# FilterSchematic_REV2.net
KiCad netlist of a schematic drawn in EAGLE
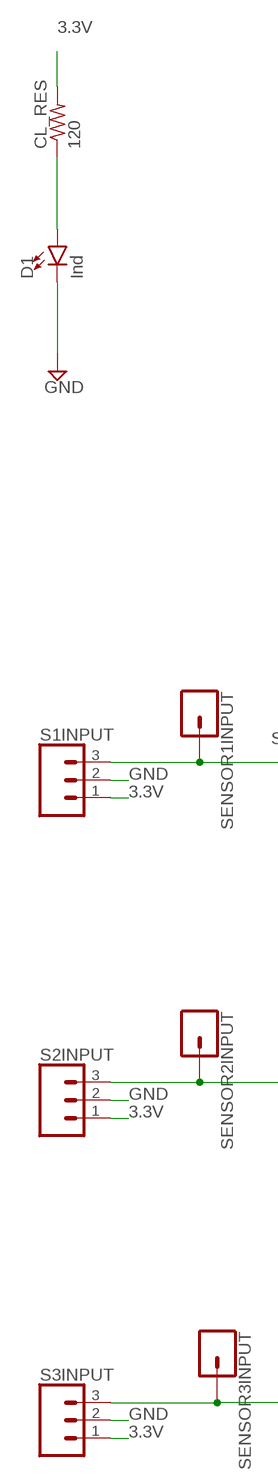
[diagram p0: schematic, sheet 1, part 1 of 2]
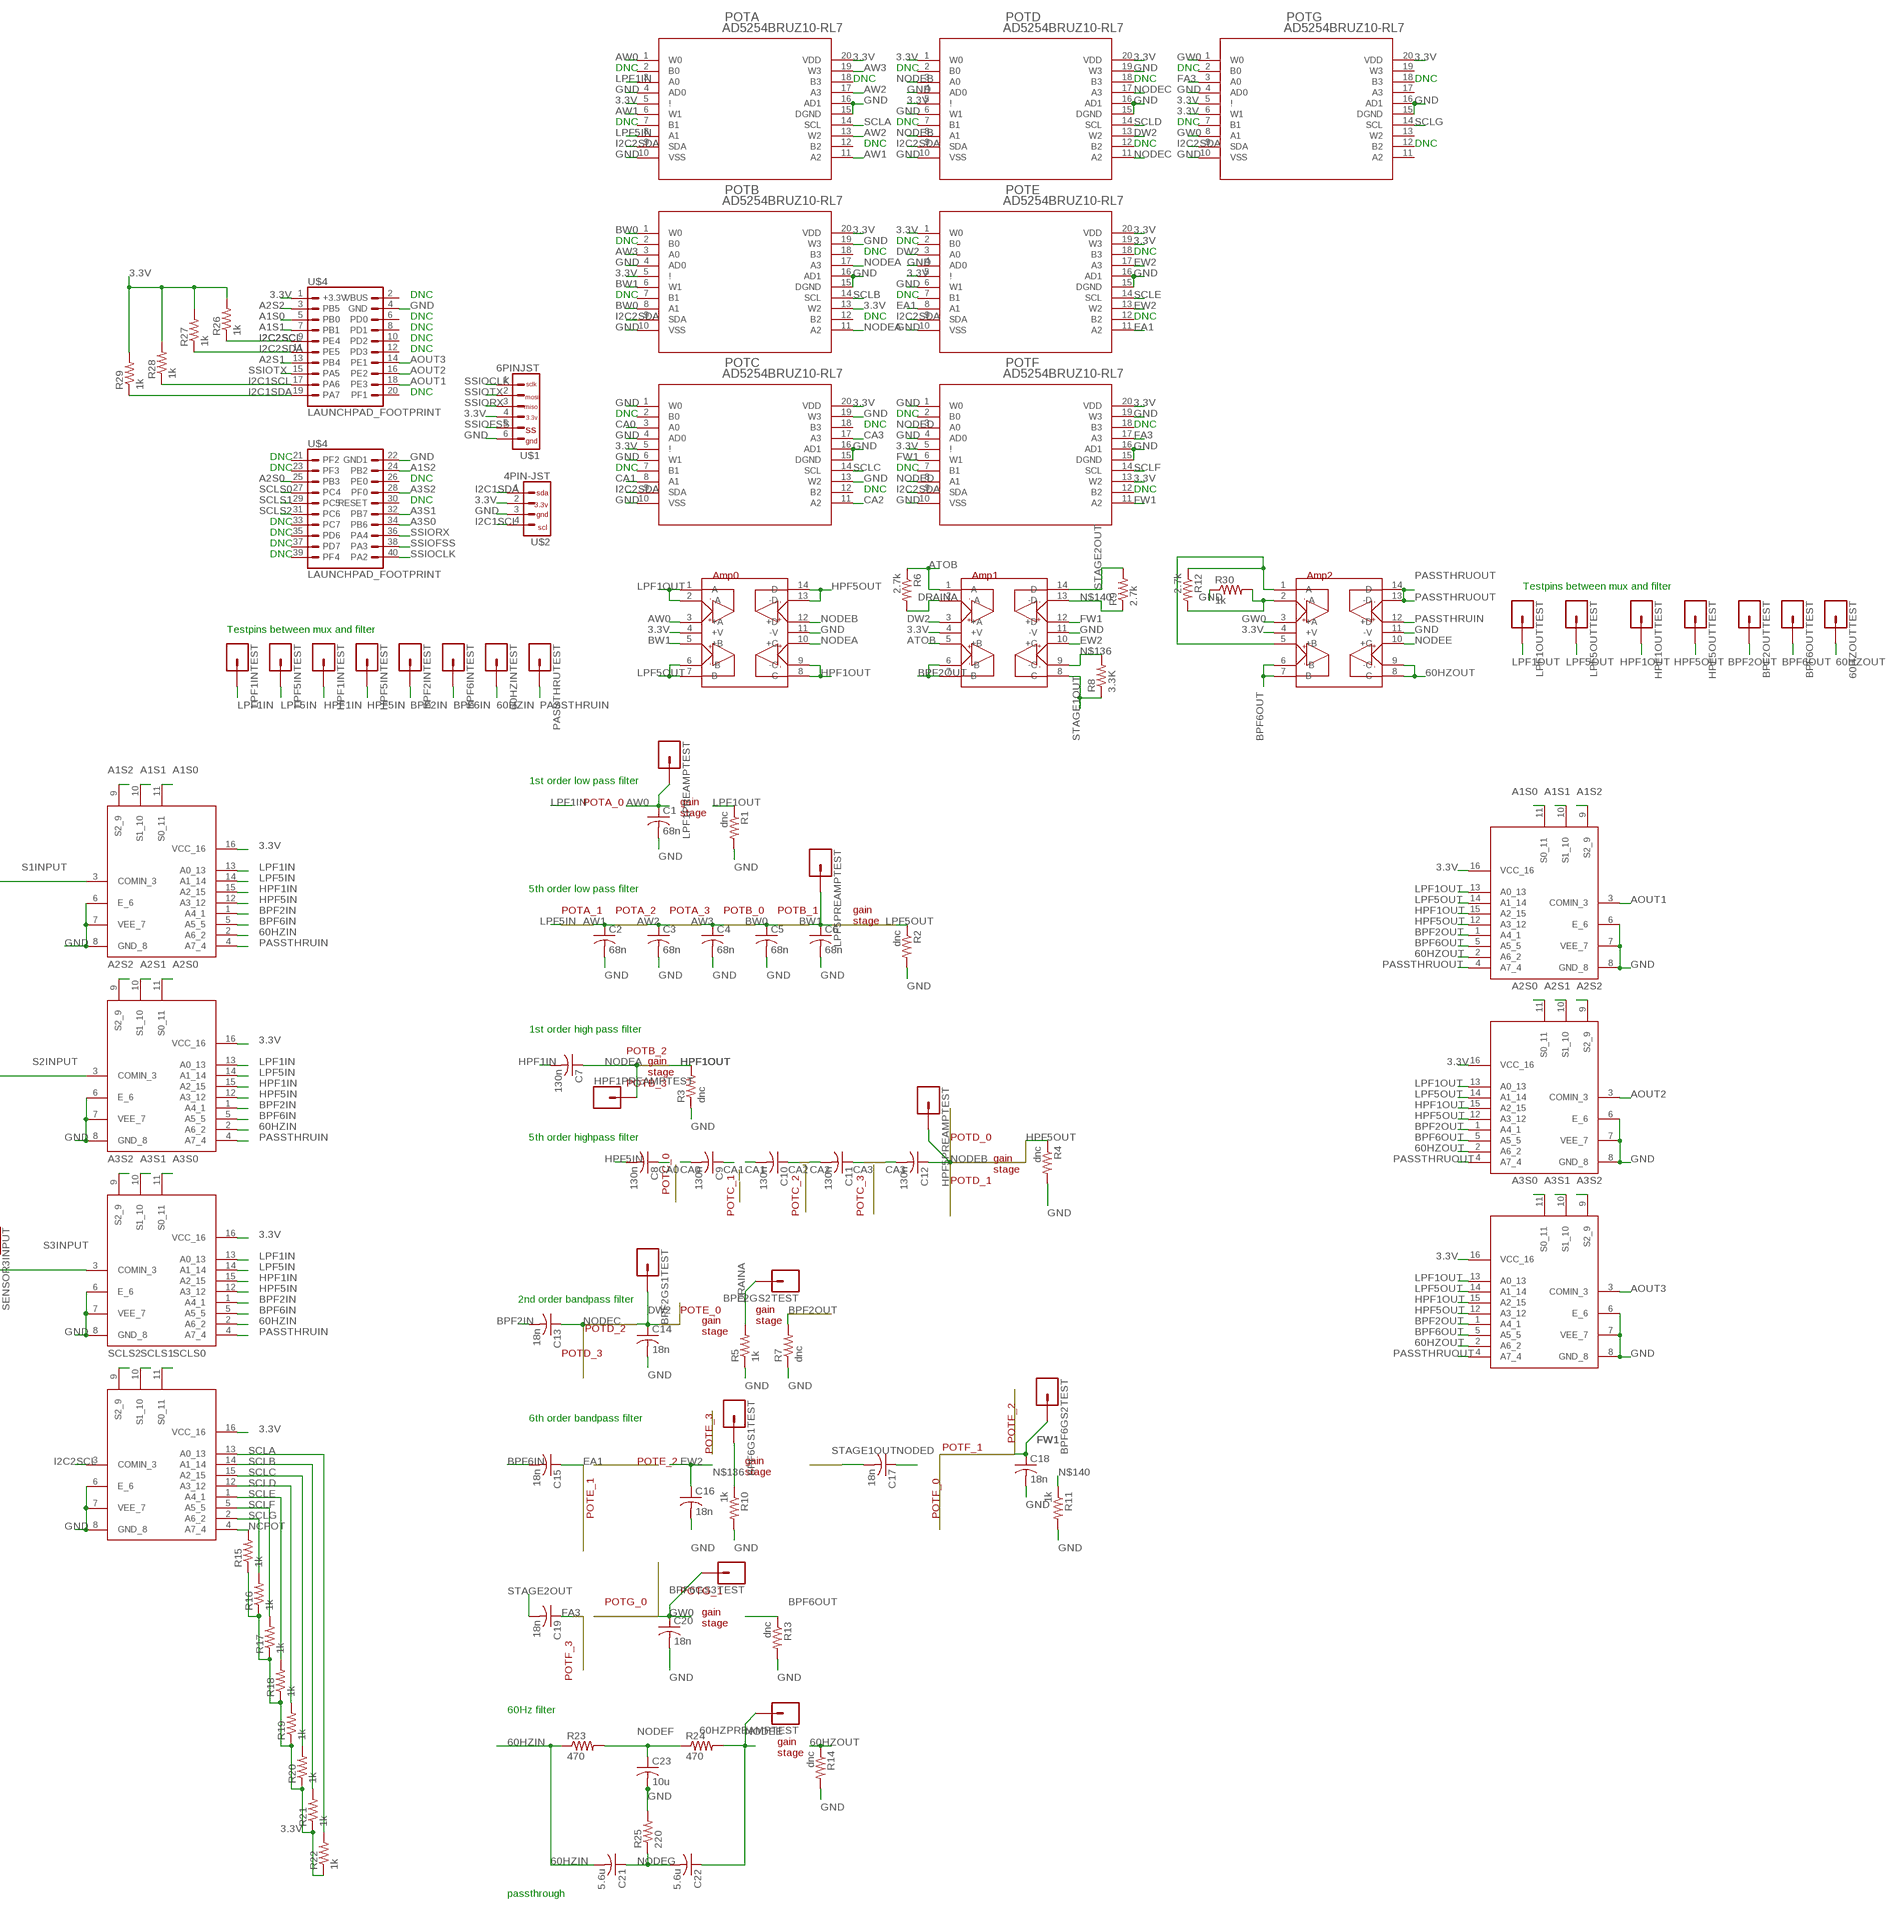
[diagram p1: schematic, sheet 1, part 2 of 2]

(export (version "E")
  (design (tool "Eeschema 10.0.6"))
  (components
    (comp (ref "60HZINTEST")
      (value "CONN_01")
      (footprint "eagle-import:1X01")
      (libsource (lib "eagle-import") (part "CONN_01"))
    )
    (comp (ref "60HZOUTTEST")
      (value "CONN_01")
      (footprint "eagle-import:1X01")
      (libsource (lib "eagle-import") (part "CONN_01"))
    )
    (comp (ref "60HZPREAMPTEST")
      (value "CONN_01")
      (footprint "eagle-import:1X01")
      (libsource (lib "eagle-import") (part "CONN_01"))
    )
    (comp (ref "A3IDEMUX")
      (value "CD74HC4051-Q1")
      (footprint "eagle-import:TSSOP16")
      (libsource (lib "eagle-import") (part "CD74HC4051-Q1"))
    )
    (comp (ref "AI1DEMUX")
      (value "CD74HC4051-Q1")
      (footprint "eagle-import:TSSOP16")
      (libsource (lib "eagle-import") (part "CD74HC4051-Q1"))
    )
    (comp (ref "AI2DEMUX")
      (value "CD74HC4051-Q1")
      (footprint "eagle-import:TSSOP16")
      (libsource (lib "eagle-import") (part "CD74HC4051-Q1"))
    )
    (comp (ref "AMP0")
      (value "OPA4830")
      (footprint "eagle-import:TSSOP14")
      (libsource (lib "eagle-import") (part "OPA4830"))
    )
    (comp (ref "AMP1")
      (value "OPA4830")
      (footprint "eagle-import:TSSOP14")
      (libsource (lib "eagle-import") (part "OPA4830"))
    )
    (comp (ref "AMP2")
      (value "OPA4830")
      (footprint "eagle-import:TSSOP14")
      (libsource (lib "eagle-import") (part "OPA4830"))
    )
    (comp (ref "AO1MUX")
      (value "CD74HC4051-Q1")
      (footprint "eagle-import:TSSOP16")
      (libsource (lib "eagle-import") (part "CD74HC4051-Q1"))
    )
    (comp (ref "AO2MUX")
      (value "CD74HC4051-Q1")
      (footprint "eagle-import:TSSOP16")
      (libsource (lib "eagle-import") (part "CD74HC4051-Q1"))
    )
    (comp (ref "AO3MUX")
      (value "CD74HC4051-Q1")
      (footprint "eagle-import:TSSOP16")
      (libsource (lib "eagle-import") (part "CD74HC4051-Q1"))
    )
    (comp (ref "BPF2GS1TEST")
      (value "CONN_01")
      (footprint "eagle-import:1X01")
      (libsource (lib "eagle-import") (part "CONN_01"))
    )
    (comp (ref "BPF2GS2TEST")
      (value "CONN_01")
      (footprint "eagle-import:1X01")
      (libsource (lib "eagle-import") (part "CONN_01"))
    )
    (comp (ref "BPF2INTEST")
      (value "CONN_01")
      (footprint "eagle-import:1X01")
      (libsource (lib "eagle-import") (part "CONN_01"))
    )
    (comp (ref "BPF2OUTTEST")
      (value "CONN_01")
      (footprint "eagle-import:1X01")
      (libsource (lib "eagle-import") (part "CONN_01"))
    )
    (comp (ref "BPF6GS1TEST")
      (value "CONN_01")
      (footprint "eagle-import:1X01")
      (libsource (lib "eagle-import") (part "CONN_01"))
    )
    (comp (ref "BPF6GS2TEST")
      (value "CONN_01")
      (footprint "eagle-import:1X01")
      (libsource (lib "eagle-import") (part "CONN_01"))
    )
    (comp (ref "BPF6GS3TEST")
      (value "CONN_01")
      (footprint "eagle-import:1X01")
      (libsource (lib "eagle-import") (part "CONN_01"))
    )
    (comp (ref "BPF6INTEST")
      (value "CONN_01")
      (footprint "eagle-import:1X01")
      (libsource (lib "eagle-import") (part "CONN_01"))
    )
    (comp (ref "BPF6OUTTEST")
      (value "CONN_01")
      (footprint "eagle-import:1X01")
      (libsource (lib "eagle-import") (part "CONN_01"))
    )
    (comp (ref "C1")
      (value "68n")
      (footprint "eagle-import:C0805")
      (libsource (lib "eagle-import") (part "C-USC0805"))
    )
    (comp (ref "C2")
      (value "68n")
      (footprint "eagle-import:C0805")
      (libsource (lib "eagle-import") (part "C-USC0805"))
    )
    (comp (ref "C3")
      (value "68n")
      (footprint "eagle-import:C0805")
      (libsource (lib "eagle-import") (part "C-USC0805"))
    )
    (comp (ref "C4")
      (value "68n")
      (footprint "eagle-import:C0805")
      (libsource (lib "eagle-import") (part "C-USC0805"))
    )
    (comp (ref "C5")
      (value "68n")
      (footprint "eagle-import:C0805")
      (libsource (lib "eagle-import") (part "C-USC0805"))
    )
    (comp (ref "C6")
      (value "68n")
      (footprint "eagle-import:C0805")
      (libsource (lib "eagle-import") (part "C-USC0805"))
    )
    (comp (ref "C7")
      (value "130n")
      (footprint "eagle-import:C0805")
      (libsource (lib "eagle-import") (part "C-USC0805"))
    )
    (comp (ref "C8")
      (value "130n")
      (footprint "eagle-import:C0805")
      (libsource (lib "eagle-import") (part "C-USC0805"))
    )
    (comp (ref "C9")
      (value "130n")
      (footprint "eagle-import:C0805")
      (libsource (lib "eagle-import") (part "C-USC0805"))
    )
    (comp (ref "C10")
      (value "130n")
      (footprint "eagle-import:C0805")
      (libsource (lib "eagle-import") (part "C-USC0805"))
    )
    (comp (ref "C11")
      (value "130n")
      (footprint "eagle-import:C0805")
      (libsource (lib "eagle-import") (part "C-USC0805"))
    )
    (comp (ref "C12")
      (value "130n")
      (footprint "eagle-import:C0805")
      (libsource (lib "eagle-import") (part "C-USC0805"))
    )
    (comp (ref "C13")
      (value "18n")
      (footprint "eagle-import:C0805")
      (libsource (lib "eagle-import") (part "C-USC0805"))
    )
    (comp (ref "C14")
      (value "18n")
      (footprint "eagle-import:C0805")
      (libsource (lib "eagle-import") (part "C-USC0805"))
    )
    (comp (ref "C15")
      (value "18n")
      (footprint "eagle-import:C0805")
      (libsource (lib "eagle-import") (part "C-USC0805"))
    )
    (comp (ref "C16")
      (value "18n")
      (footprint "eagle-import:C0805")
      (libsource (lib "eagle-import") (part "C-USC0805"))
    )
    (comp (ref "C17")
      (value "18n")
      (footprint "eagle-import:C0805")
      (libsource (lib "eagle-import") (part "C-USC0805"))
    )
    (comp (ref "C18")
      (value "18n")
      (footprint "eagle-import:C0805")
      (libsource (lib "eagle-import") (part "C-USC0805"))
    )
    (comp (ref "C19")
      (value "18n")
      (footprint "eagle-import:C0805")
      (libsource (lib "eagle-import") (part "C-USC0805"))
    )
    (comp (ref "C20")
      (value "18n")
      (footprint "eagle-import:C0805")
      (libsource (lib "eagle-import") (part "C-USC0805"))
    )
    (comp (ref "C21")
      (value "5.6u")
      (footprint "eagle-import:C0805")
      (libsource (lib "eagle-import") (part "C-USC0805"))
    )
    (comp (ref "C22")
      (value "5.6u")
      (footprint "eagle-import:C0805")
      (libsource (lib "eagle-import") (part "C-USC0805"))
    )
    (comp (ref "C23")
      (value "10u")
      (footprint "eagle-import:C0805")
      (libsource (lib "eagle-import") (part "C-USC0805"))
    )
    (comp (ref "CL_RES")
      (value "120")
      (footprint "eagle-import:R0805")
      (libsource (lib "eagle-import") (part "rcl_334_R-US_R0805"))
    )
    (comp (ref "D1")
      (value "Ind")
      (footprint "eagle-import:LED-0603")
      (libsource (lib "eagle-import") (part "LED-GREEN0603"))
    )
    (comp (ref "HPF1INTEST")
      (value "CONN_01")
      (footprint "eagle-import:1X01")
      (libsource (lib "eagle-import") (part "CONN_01"))
    )
    (comp (ref "HPF1OUTTEST")
      (value "CONN_01")
      (footprint "eagle-import:1X01")
      (libsource (lib "eagle-import") (part "CONN_01"))
    )
    (comp (ref "HPF1PREAMPTEST")
      (value "CONN_01")
      (footprint "eagle-import:1X01")
      (libsource (lib "eagle-import") (part "CONN_01"))
    )
    (comp (ref "HPF5INTEST")
      (value "CONN_01")
      (footprint "eagle-import:1X01")
      (libsource (lib "eagle-import") (part "CONN_01"))
    )
    (comp (ref "HPF5OUTTEST")
      (value "CONN_01")
      (footprint "eagle-import:1X01")
      (libsource (lib "eagle-import") (part "CONN_01"))
    )
    (comp (ref "HPF5PREAMPTEST")
      (value "CONN_01")
      (footprint "eagle-import:1X01")
      (libsource (lib "eagle-import") (part "CONN_01"))
    )
    (comp (ref "LPF1INTEST")
      (value "CONN_01")
      (footprint "eagle-import:1X01")
      (libsource (lib "eagle-import") (part "CONN_01"))
    )
    (comp (ref "LPF1OUTTEST")
      (value "CONN_01")
      (footprint "eagle-import:1X01")
      (libsource (lib "eagle-import") (part "CONN_01"))
    )
    (comp (ref "LPF1PREAMPTEST")
      (value "CONN_01")
      (footprint "eagle-import:1X01")
      (libsource (lib "eagle-import") (part "CONN_01"))
    )
    (comp (ref "LPF5INTEST")
      (value "CONN_01")
      (footprint "eagle-import:1X01")
      (libsource (lib "eagle-import") (part "CONN_01"))
    )
    (comp (ref "LPF5OUTTEST")
      (value "CONN_01")
      (footprint "eagle-import:1X01")
      (libsource (lib "eagle-import") (part "CONN_01"))
    )
    (comp (ref "LPF5PREAMPTEST")
      (value "CONN_01")
      (footprint "eagle-import:1X01")
      (libsource (lib "eagle-import") (part "CONN_01"))
    )
    (comp (ref "PASSTHRUTEST")
      (value "CONN_01")
      (footprint "eagle-import:1X01")
      (libsource (lib "eagle-import") (part "CONN_01"))
    )
    (comp (ref "POTA")
      (value "AD5254BRUZ10-RL7")
      (footprint "eagle-import:RU_20")
      (fields (field (name "MANUFACTURER_PART_NUMBER") "AD5254BRUZ10RL7"))
      (libsource (lib "eagle-import") (part "AD5254BRUZ10-RL7"))
    )
    (comp (ref "POTB")
      (value "AD5254BRUZ10-RL7")
      (footprint "eagle-import:RU_20")
      (fields (field (name "MANUFACTURER_PART_NUMBER") "AD5254BRUZ10RL7"))
      (libsource (lib "eagle-import") (part "AD5254BRUZ10-RL7"))
    )
    (comp (ref "POTC")
      (value "AD5254BRUZ10-RL7")
      (footprint "eagle-import:RU_20")
      (fields (field (name "MANUFACTURER_PART_NUMBER") "AD5254BRUZ10RL7"))
      (libsource (lib "eagle-import") (part "AD5254BRUZ10-RL7"))
    )
    (comp (ref "POTD")
      (value "AD5254BRUZ10-RL7")
      (footprint "eagle-import:RU_20")
      (fields (field (name "MANUFACTURER_PART_NUMBER") "AD5254BRUZ10RL7"))
      (libsource (lib "eagle-import") (part "AD5254BRUZ10-RL7"))
    )
    (comp (ref "POTE")
      (value "AD5254BRUZ10-RL7")
      (footprint "eagle-import:RU_20")
      (fields (field (name "MANUFACTURER_PART_NUMBER") "AD5254BRUZ10RL7"))
      (libsource (lib "eagle-import") (part "AD5254BRUZ10-RL7"))
    )
    (comp (ref "POTF")
      (value "AD5254BRUZ10-RL7")
      (footprint "eagle-import:RU_20")
      (fields (field (name "MANUFACTURER_PART_NUMBER") "AD5254BRUZ10RL7"))
      (libsource (lib "eagle-import") (part "AD5254BRUZ10-RL7"))
    )
    (comp (ref "POTG")
      (value "AD5254BRUZ10-RL7")
      (footprint "eagle-import:RU_20")
      (fields (field (name "MANUFACTURER_PART_NUMBER") "AD5254BRUZ10RL7"))
      (libsource (lib "eagle-import") (part "AD5254BRUZ10-RL7"))
    )
    (comp (ref "R1")
      (value "dnc")
      (footprint "eagle-import:R0805")
      (libsource (lib "eagle-import") (part "rcl_334_R-US_R0805"))
    )
    (comp (ref "R2")
      (value "dnc")
      (footprint "eagle-import:R0805")
      (libsource (lib "eagle-import") (part "rcl_334_R-US_R0805"))
    )
    (comp (ref "R3")
      (value "dnc")
      (footprint "eagle-import:R0805")
      (libsource (lib "eagle-import") (part "rcl_334_R-US_R0805"))
    )
    (comp (ref "R4")
      (value "dnc")
      (footprint "eagle-import:R0805")
      (libsource (lib "eagle-import") (part "rcl_334_R-US_R0805"))
    )
    (comp (ref "R5")
      (value "1k")
      (footprint "eagle-import:R0805")
      (libsource (lib "eagle-import") (part "rcl_334_R-US_R0805"))
    )
    (comp (ref "R6")
      (value "2.7k")
      (footprint "eagle-import:R0805")
      (libsource (lib "eagle-import") (part "rcl_334_R-US_R0805"))
    )
    (comp (ref "R7")
      (value "dnc")
      (footprint "eagle-import:R0805")
      (libsource (lib "eagle-import") (part "rcl_334_R-US_R0805"))
    )
    (comp (ref "R8")
      (value "3.3K")
      (footprint "eagle-import:R0805")
      (libsource (lib "eagle-import") (part "rcl_334_R-US_R0805"))
    )
    (comp (ref "R9")
      (value "2.7k")
      (footprint "eagle-import:R0805")
      (libsource (lib "eagle-import") (part "rcl_334_R-US_R0805"))
    )
    (comp (ref "R10")
      (value "1k")
      (footprint "eagle-import:R0805")
      (libsource (lib "eagle-import") (part "rcl_334_R-US_R0805"))
    )
    (comp (ref "R11")
      (value "1k")
      (footprint "eagle-import:R0805")
      (libsource (lib "eagle-import") (part "rcl_334_R-US_R0805"))
    )
    (comp (ref "R12")
      (value "2.7k")
      (footprint "eagle-import:R0805")
      (libsource (lib "eagle-import") (part "rcl_334_R-US_R0805"))
    )
    (comp (ref "R13")
      (value "dnc")
      (footprint "eagle-import:R0805")
      (libsource (lib "eagle-import") (part "rcl_334_R-US_R0805"))
    )
    (comp (ref "R14")
      (value "dnc")
      (footprint "eagle-import:R0805")
      (libsource (lib "eagle-import") (part "rcl_334_R-US_R0805"))
    )
    (comp (ref "R15")
      (value "1k")
      (footprint "eagle-import:R0805")
      (libsource (lib "eagle-import") (part "rcl_334_R-US_R0805"))
    )
    (comp (ref "R16")
      (value "1k")
      (footprint "eagle-import:R0805")
      (libsource (lib "eagle-import") (part "rcl_334_R-US_R0805"))
    )
    (comp (ref "R17")
      (value "1k")
      (footprint "eagle-import:R0805")
      (libsource (lib "eagle-import") (part "rcl_334_R-US_R0805"))
    )
    (comp (ref "R18")
      (value "1k")
      (footprint "eagle-import:R0805")
      (libsource (lib "eagle-import") (part "rcl_334_R-US_R0805"))
    )
    (comp (ref "R19")
      (value "1k")
      (footprint "eagle-import:R0805")
      (libsource (lib "eagle-import") (part "rcl_334_R-US_R0805"))
    )
    (comp (ref "R20")
      (value "1k")
      (footprint "eagle-import:R0805")
      (libsource (lib "eagle-import") (part "rcl_334_R-US_R0805"))
    )
    (comp (ref "R21")
      (value "1k")
      (footprint "eagle-import:R0805")
      (libsource (lib "eagle-import") (part "rcl_334_R-US_R0805"))
    )
    (comp (ref "R22")
      (value "1k")
      (footprint "eagle-import:R0805")
      (libsource (lib "eagle-import") (part "rcl_334_R-US_R0805"))
    )
    (comp (ref "R23")
      (value "470")
      (footprint "eagle-import:R0805")
      (libsource (lib "eagle-import") (part "R-US_R0805"))
    )
    (comp (ref "R24")
      (value "470")
      (footprint "eagle-import:R0805")
      (libsource (lib "eagle-import") (part "R-US_R0805"))
    )
    (comp (ref "R25")
      (value "220")
      (footprint "eagle-import:R0805")
      (libsource (lib "eagle-import") (part "R-US_R0805"))
    )
    (comp (ref "R26")
      (value "1k")
      (footprint "eagle-import:R0805")
      (libsource (lib "eagle-import") (part "rcl_334_R-US_R0805"))
    )
    (comp (ref "R27")
      (value "1k")
      (footprint "eagle-import:R0805")
      (libsource (lib "eagle-import") (part "rcl_334_R-US_R0805"))
    )
    (comp (ref "R28")
      (value "1k")
      (footprint "eagle-import:R0805")
      (libsource (lib "eagle-import") (part "rcl_334_R-US_R0805"))
    )
    (comp (ref "R29")
      (value "1k")
      (footprint "eagle-import:R0805")
      (libsource (lib "eagle-import") (part "rcl_334_R-US_R0805"))
    )
    (comp (ref "R30")
      (value "1k")
      (footprint "eagle-import:R0805")
      (libsource (lib "eagle-import") (part "rcl_334_R-US_R0805"))
    )
    (comp (ref "S1INPUT")
      (value "CONN_03JST-PTH-VERT")
      (footprint "eagle-import:JST-3-PTH-VERT")
      (libsource (lib "eagle-import") (part "CONN_03JST-PTH-VERT"))
    )
    (comp (ref "S2INPUT")
      (value "CONN_03JST-PTH-VERT")
      (footprint "eagle-import:JST-3-PTH-VERT")
      (libsource (lib "eagle-import") (part "CONN_03JST-PTH-VERT"))
    )
    (comp (ref "S3INPUT")
      (value "CONN_03JST-PTH-VERT")
      (footprint "eagle-import:JST-3-PTH-VERT")
      (libsource (lib "eagle-import") (part "CONN_03JST-PTH-VERT"))
    )
    (comp (ref "SCLMUX")
      (value "CD74HC4051-Q1")
      (footprint "eagle-import:TSSOP16")
      (libsource (lib "eagle-import") (part "CD74HC4051-Q1"))
    )
    (comp (ref "SENSOR1INPUT")
      (value "CONN_01")
      (footprint "eagle-import:1X01")
      (libsource (lib "eagle-import") (part "CONN_01"))
    )
    (comp (ref "SENSOR2INPUT")
      (value "CONN_01")
      (footprint "eagle-import:1X01")
      (libsource (lib "eagle-import") (part "CONN_01"))
    )
    (comp (ref "SENSOR3INPUT")
      (value "CONN_01")
      (footprint "eagle-import:1X01")
      (libsource (lib "eagle-import") (part "CONN_01"))
    )
    (comp (ref "U$1")
      (value "6PINJST")
      (footprint "eagle-import:JST-6-PTH-VERT")
      (libsource (lib "eagle-import") (part "6PINJST"))
    )
    (comp (ref "U$2")
      (value "4PIN-JST")
      (footprint "eagle-import:JST-4-PTH-VERT")
      (libsource (lib "eagle-import") (part "4PIN-JST"))
    )
    (comp (ref "U$4")
      (value "LAUNCHPAD_FOOTPRINT")
      (footprint "eagle-import:SSW-110-02-S-D")
      (libsource (lib "eagle-import") (part "LAUNCHPAD_FOOTPRINT"))
    )
  )
  (nets
    (net (code "1") (name "/3.3V") (class "Default")
      (node (ref "A3IDEMUX") (pin "16") (pinfunction "VCC_16_16") (pintype "bidirectional"))
      (node (ref "AI1DEMUX") (pin "16") (pinfunction "VCC_16_16") (pintype "bidirectional"))
      (node (ref "AI2DEMUX") (pin "16") (pinfunction "VCC_16_16") (pintype "bidirectional"))
      (node (ref "AMP0") (pin "4") (pinfunction "+V_4") (pintype "bidirectional"))
      (node (ref "AMP1") (pin "4") (pinfunction "+V_4") (pintype "bidirectional"))
      (node (ref "AMP2") (pin "4") (pinfunction "+V_4") (pintype "bidirectional"))
      (node (ref "AO1MUX") (pin "16") (pinfunction "VCC_16_16") (pintype "bidirectional"))
      (node (ref "AO2MUX") (pin "16") (pinfunction "VCC_16_16") (pintype "bidirectional"))
      (node (ref "AO3MUX") (pin "16") (pinfunction "VCC_16_16") (pintype "bidirectional"))
      (node (ref "CL_RES") (pin "2") (pinfunction "2_2") (pintype "passive"))
      (node (ref "POTA") (pin "20") (pinfunction "VDD_20") (pintype "power_in"))
      (node (ref "POTA") (pin "5") (pinfunction "~_5") (pintype "passive"))
      (node (ref "POTB") (pin "13") (pinfunction "W2_13") (pintype "passive"))
      (node (ref "POTB") (pin "20") (pinfunction "VDD_20") (pintype "power_in"))
      (node (ref "POTB") (pin "5") (pinfunction "~_5") (pintype "passive"))
      (node (ref "POTC") (pin "20") (pinfunction "VDD_20") (pintype "power_in"))
      (node (ref "POTC") (pin "5") (pinfunction "~_5") (pintype "passive"))
      (node (ref "POTD") (pin "1") (pinfunction "W0_1") (pintype "passive"))
      (node (ref "POTD") (pin "20") (pinfunction "VDD_20") (pintype "power_in"))
      (node (ref "POTD") (pin "5") (pinfunction "~_5") (pintype "passive"))
      (node (ref "POTE") (pin "1") (pinfunction "W0_1") (pintype "passive"))
      (node (ref "POTE") (pin "19") (pinfunction "W3_19") (pintype "passive"))
      (node (ref "POTE") (pin "20") (pinfunction "VDD_20") (pintype "power_in"))
      (node (ref "POTE") (pin "5") (pinfunction "~_5") (pintype "passive"))
      (node (ref "POTF") (pin "13") (pinfunction "W2_13") (pintype "passive"))
      (node (ref "POTF") (pin "20") (pinfunction "VDD_20") (pintype "power_in"))
      (node (ref "POTF") (pin "5") (pinfunction "~_5") (pintype "passive"))
      (node (ref "POTG") (pin "20") (pinfunction "VDD_20") (pintype "power_in"))
      (node (ref "POTG") (pin "5") (pinfunction "~_5") (pintype "passive"))
      (node (ref "POTG") (pin "6") (pinfunction "W1_6") (pintype "passive"))
      (node (ref "R15") (pin "1") (pinfunction "1_1") (pintype "passive"))
      (node (ref "R16") (pin "1") (pinfunction "1_1") (pintype "passive"))
      (node (ref "R17") (pin "1") (pinfunction "1_1") (pintype "passive"))
      (node (ref "R18") (pin "1") (pinfunction "1_1") (pintype "passive"))
      (node (ref "R19") (pin "1") (pinfunction "1_1") (pintype "passive"))
      (node (ref "R20") (pin "1") (pinfunction "1_1") (pintype "passive"))
      (node (ref "R21") (pin "1") (pinfunction "1_1") (pintype "passive"))
      (node (ref "R22") (pin "1") (pinfunction "1_1") (pintype "passive"))
      (node (ref "R26") (pin "2") (pinfunction "2_2") (pintype "passive"))
      (node (ref "R27") (pin "2") (pinfunction "2_2") (pintype "passive"))
      (node (ref "R28") (pin "2") (pinfunction "2_2") (pintype "passive"))
      (node (ref "R29") (pin "2") (pinfunction "2_2") (pintype "passive"))
      (node (ref "S1INPUT") (pin "1") (pinfunction "1_1") (pintype "passive"))
      (node (ref "S2INPUT") (pin "1") (pinfunction "1_1") (pintype "passive"))
      (node (ref "S3INPUT") (pin "1") (pinfunction "1_1") (pintype "passive"))
      (node (ref "SCLMUX") (pin "16") (pinfunction "VCC_16_16") (pintype "bidirectional"))
      (node (ref "U$1") (pin "4") (pinfunction "4_4") (pintype "passive"))
      (node (ref "U$2") (pin "2") (pinfunction "2_2") (pintype "passive"))
      (node (ref "U$4") (pin "1") (pinfunction "+3.3V_1") (pintype "passive"))
    )
    (net (code "2") (name "/60HZIN") (class "Default")
      (node (ref "60HZINTEST") (pin "1") (pinfunction "1_1") (pintype "passive"))
      (node (ref "A3IDEMUX") (pin "2") (pinfunction "A6_2_2") (pintype "bidirectional"))
      (node (ref "AI1DEMUX") (pin "2") (pinfunction "A6_2_2") (pintype "bidirectional"))
      (node (ref "AI2DEMUX") (pin "2") (pinfunction "A6_2_2") (pintype "bidirectional"))
      (node (ref "C21") (pin "2") (pinfunction "2_2") (pintype "passive"))
      (node (ref "R23") (pin "1") (pinfunction "1_1") (pintype "passive"))
    )
    (net (code "3") (name "/60HZOUT") (class "Default")
      (node (ref "60HZOUTTEST") (pin "1") (pinfunction "1_1") (pintype "passive"))
      (node (ref "AMP2") (pin "8") (pinfunction "C_8") (pintype "bidirectional"))
      (node (ref "AMP2") (pin "9") (pinfunction "-C_9") (pintype "bidirectional"))
      (node (ref "AO1MUX") (pin "2") (pinfunction "A6_2_2") (pintype "bidirectional"))
      (node (ref "AO2MUX") (pin "2") (pinfunction "A6_2_2") (pintype "bidirectional"))
      (node (ref "AO3MUX") (pin "2") (pinfunction "A6_2_2") (pintype "bidirectional"))
      (node (ref "R14") (pin "1") (pinfunction "1_1") (pintype "passive"))
    )
    (net (code "4") (name "/A1S0") (class "Default")
      (node (ref "AI1DEMUX") (pin "11") (pinfunction "S0_11_11") (pintype "bidirectional"))
      (node (ref "AO1MUX") (pin "11") (pinfunction "S0_11_11") (pintype "bidirectional"))
      (node (ref "U$4") (pin "5") (pinfunction "PB0_5") (pintype "passive"))
    )
    (net (code "5") (name "/A1S1") (class "Default")
      (node (ref "AI1DEMUX") (pin "10") (pinfunction "S1_10_10") (pintype "bidirectional"))
      (node (ref "AO1MUX") (pin "10") (pinfunction "S1_10_10") (pintype "bidirectional"))
      (node (ref "U$4") (pin "7") (pinfunction "PB1_7") (pintype "passive"))
    )
    (net (code "6") (name "/A1S2") (class "Default")
      (node (ref "AI1DEMUX") (pin "9") (pinfunction "S2_9_9") (pintype "bidirectional"))
      (node (ref "AO1MUX") (pin "9") (pinfunction "S2_9_9") (pintype "bidirectional"))
      (node (ref "U$4") (pin "24") (pinfunction "PB2_24") (pintype "passive"))
    )
    (net (code "7") (name "/A2S0") (class "Default")
      (node (ref "AI2DEMUX") (pin "11") (pinfunction "S0_11_11") (pintype "bidirectional"))
      (node (ref "AO2MUX") (pin "11") (pinfunction "S0_11_11") (pintype "bidirectional"))
      (node (ref "U$4") (pin "25") (pinfunction "PB3_25") (pintype "passive"))
    )
    (net (code "8") (name "/A2S1") (class "Default")
      (node (ref "AI2DEMUX") (pin "10") (pinfunction "S1_10_10") (pintype "bidirectional"))
      (node (ref "AO2MUX") (pin "10") (pinfunction "S1_10_10") (pintype "bidirectional"))
      (node (ref "U$4") (pin "13") (pinfunction "PB4_13") (pintype "passive"))
    )
    (net (code "9") (name "/A2S2") (class "Default")
      (node (ref "AI2DEMUX") (pin "9") (pinfunction "S2_9_9") (pintype "bidirectional"))
      (node (ref "AO2MUX") (pin "9") (pinfunction "S2_9_9") (pintype "bidirectional"))
      (node (ref "U$4") (pin "3") (pinfunction "PB5_3") (pintype "passive"))
    )
    (net (code "10") (name "/A3S0") (class "Default")
      (node (ref "A3IDEMUX") (pin "11") (pinfunction "S0_11_11") (pintype "bidirectional"))
      (node (ref "AO3MUX") (pin "11") (pinfunction "S0_11_11") (pintype "bidirectional"))
      (node (ref "U$4") (pin "34") (pinfunction "PB6_34") (pintype "passive"))
    )
    (net (code "11") (name "/A3S1") (class "Default")
      (node (ref "A3IDEMUX") (pin "10") (pinfunction "S1_10_10") (pintype "bidirectional"))
      (node (ref "AO3MUX") (pin "10") (pinfunction "S1_10_10") (pintype "bidirectional"))
      (node (ref "U$4") (pin "32") (pinfunction "PB7_32") (pintype "passive"))
    )
    (net (code "12") (name "/A3S2") (class "Default")
      (node (ref "A3IDEMUX") (pin "9") (pinfunction "S2_9_9") (pintype "bidirectional"))
      (node (ref "AO3MUX") (pin "9") (pinfunction "S2_9_9") (pintype "bidirectional"))
      (node (ref "U$4") (pin "28") (pinfunction "PF0_28") (pintype "passive"))
    )
    (net (code "13") (name "/AOUT1") (class "Default")
      (node (ref "AO1MUX") (pin "3") (pinfunction "COMIN_3_3") (pintype "bidirectional"))
      (node (ref "U$4") (pin "18") (pinfunction "PE3_18") (pintype "passive"))
    )
    (net (code "14") (name "/AOUT2") (class "Default")
      (node (ref "AO2MUX") (pin "3") (pinfunction "COMIN_3_3") (pintype "bidirectional"))
      (node (ref "U$4") (pin "16") (pinfunction "PE2_16") (pintype "passive"))
    )
    (net (code "15") (name "/AOUT3") (class "Default")
      (node (ref "AO3MUX") (pin "3") (pinfunction "COMIN_3_3") (pintype "bidirectional"))
      (node (ref "U$4") (pin "14") (pinfunction "PE1_14") (pintype "passive"))
    )
    (net (code "16") (name "/ATOB") (class "Default")
      (node (ref "AMP1") (pin "1") (pinfunction "A_1") (pintype "bidirectional"))
      (node (ref "AMP1") (pin "5") (pinfunction "+B_5") (pintype "bidirectional"))
      (node (ref "R6") (pin "1") (pinfunction "1_1") (pintype "passive"))
    )
    (net (code "17") (name "/AW0") (class "Default")
      (node (ref "AMP0") (pin "3") (pinfunction "+A_3") (pintype "bidirectional"))
      (node (ref "C1") (pin "1") (pinfunction "1_1") (pintype "passive"))
      (node (ref "LPF1PREAMPTEST") (pin "1") (pinfunction "1_1") (pintype "passive"))
      (node (ref "POTA") (pin "1") (pinfunction "W0_1") (pintype "passive"))
    )
    (net (code "18") (name "/AW1") (class "Default")
      (node (ref "C2") (pin "1") (pinfunction "1_1") (pintype "passive"))
      (node (ref "POTA") (pin "11") (pinfunction "A2_11") (pintype "passive"))
      (node (ref "POTA") (pin "6") (pinfunction "W1_6") (pintype "passive"))
    )
    (net (code "19") (name "/AW2") (class "Default")
      (node (ref "C3") (pin "1") (pinfunction "1_1") (pintype "passive"))
      (node (ref "POTA") (pin "13") (pinfunction "W2_13") (pintype "passive"))
      (node (ref "POTA") (pin "17") (pinfunction "A3_17") (pintype "passive"))
    )
    (net (code "20") (name "/AW3") (class "Default")
      (node (ref "C4") (pin "1") (pinfunction "1_1") (pintype "passive"))
      (node (ref "POTA") (pin "19") (pinfunction "W3_19") (pintype "passive"))
      (node (ref "POTB") (pin "3") (pinfunction "A0_3") (pintype "passive"))
    )
    (net (code "21") (name "/BPF2IN") (class "Default")
      (node (ref "A3IDEMUX") (pin "1") (pinfunction "A4_1_1") (pintype "bidirectional"))
      (node (ref "AI1DEMUX") (pin "1") (pinfunction "A4_1_1") (pintype "bidirectional"))
      (node (ref "AI2DEMUX") (pin "1") (pinfunction "A4_1_1") (pintype "bidirectional"))
      (node (ref "BPF2INTEST") (pin "1") (pinfunction "1_1") (pintype "passive"))
      (node (ref "C13") (pin "2") (pinfunction "2_2") (pintype "passive"))
    )
    (net (code "22") (name "/BPF2OUT") (class "Default")
      (node (ref "AMP1") (pin "6") (pinfunction "-B_6") (pintype "bidirectional"))
      (node (ref "AMP1") (pin "7") (pinfunction "B_7") (pintype "bidirectional"))
      (node (ref "AO1MUX") (pin "1") (pinfunction "A4_1_1") (pintype "bidirectional"))
      (node (ref "AO2MUX") (pin "1") (pinfunction "A4_1_1") (pintype "bidirectional"))
      (node (ref "AO3MUX") (pin "1") (pinfunction "A4_1_1") (pintype "bidirectional"))
      (node (ref "BPF2OUTTEST") (pin "1") (pinfunction "1_1") (pintype "passive"))
      (node (ref "R7") (pin "2") (pinfunction "2_2") (pintype "passive"))
    )
    (net (code "23") (name "/BPF6IN") (class "Default")
      (node (ref "A3IDEMUX") (pin "5") (pinfunction "A5_5_5") (pintype "bidirectional"))
      (node (ref "AI1DEMUX") (pin "5") (pinfunction "A5_5_5") (pintype "bidirectional"))
      (node (ref "AI2DEMUX") (pin "5") (pinfunction "A5_5_5") (pintype "bidirectional"))
      (node (ref "BPF6INTEST") (pin "1") (pinfunction "1_1") (pintype "passive"))
      (node (ref "C15") (pin "2") (pinfunction "2_2") (pintype "passive"))
    )
    (net (code "24") (name "/BPF6OUT") (class "Default")
      (node (ref "AMP2") (pin "6") (pinfunction "-B_6") (pintype "bidirectional"))
      (node (ref "AMP2") (pin "7") (pinfunction "B_7") (pintype "bidirectional"))
      (node (ref "AO1MUX") (pin "5") (pinfunction "A5_5_5") (pintype "bidirectional"))
      (node (ref "AO2MUX") (pin "5") (pinfunction "A5_5_5") (pintype "bidirectional"))
      (node (ref "AO3MUX") (pin "5") (pinfunction "A5_5_5") (pintype "bidirectional"))
      (node (ref "BPF6OUTTEST") (pin "1") (pinfunction "1_1") (pintype "passive"))
      (node (ref "R13") (pin "1") (pinfunction "1_1") (pintype "passive"))
    )
    (net (code "25") (name "/BW0") (class "Default")
      (node (ref "C5") (pin "1") (pinfunction "1_1") (pintype "passive"))
      (node (ref "POTB") (pin "1") (pinfunction "W0_1") (pintype "passive"))
      (node (ref "POTB") (pin "8") (pinfunction "A1_8") (pintype "passive"))
    )
    (net (code "26") (name "/BW1") (class "Default")
      (node (ref "AMP0") (pin "5") (pinfunction "+B_5") (pintype "bidirectional"))
      (node (ref "C6") (pin "1") (pinfunction "1_1") (pintype "passive"))
      (node (ref "LPF5PREAMPTEST") (pin "1") (pinfunction "1_1") (pintype "passive"))
      (node (ref "POTB") (pin "6") (pinfunction "W1_6") (pintype "passive"))
    )
    (net (code "27") (name "/CA0") (class "Default")
      (node (ref "C8") (pin "1") (pinfunction "1_1") (pintype "passive"))
      (node (ref "C9") (pin "2") (pinfunction "2_2") (pintype "passive"))
      (node (ref "POTC") (pin "3") (pinfunction "A0_3") (pintype "passive"))
    )
    (net (code "28") (name "/CA1") (class "Default")
      (node (ref "C10") (pin "2") (pinfunction "2_2") (pintype "passive"))
      (node (ref "C9") (pin "1") (pinfunction "1_1") (pintype "passive"))
      (node (ref "POTC") (pin "8") (pinfunction "A1_8") (pintype "passive"))
    )
    (net (code "29") (name "/CA2") (class "Default")
      (node (ref "C10") (pin "1") (pinfunction "1_1") (pintype "passive"))
      (node (ref "C11") (pin "2") (pinfunction "2_2") (pintype "passive"))
      (node (ref "POTC") (pin "11") (pinfunction "A2_11") (pintype "passive"))
    )
    (net (code "30") (name "/CA3") (class "Default")
      (node (ref "C11") (pin "1") (pinfunction "1_1") (pintype "passive"))
      (node (ref "C12") (pin "2") (pinfunction "2_2") (pintype "passive"))
      (node (ref "POTC") (pin "17") (pinfunction "A3_17") (pintype "passive"))
    )
    (net (code "31") (name "/DRAINA") (class "Default")
      (node (ref "AMP1") (pin "2") (pinfunction "-A_2") (pintype "bidirectional"))
      (node (ref "BPF2GS2TEST") (pin "1") (pinfunction "1_1") (pintype "passive"))
      (node (ref "R5") (pin "2") (pinfunction "2_2") (pintype "passive"))
      (node (ref "R6") (pin "2") (pinfunction "2_2") (pintype "passive"))
    )
    (net (code "32") (name "/DW2") (class "Default")
      (node (ref "AMP1") (pin "3") (pinfunction "+A_3") (pintype "bidirectional"))
      (node (ref "BPF2GS1TEST") (pin "1") (pinfunction "1_1") (pintype "passive"))
      (node (ref "C14") (pin "1") (pinfunction "1_1") (pintype "passive"))
      (node (ref "POTD") (pin "13") (pinfunction "W2_13") (pintype "passive"))
      (node (ref "POTE") (pin "3") (pinfunction "A0_3") (pintype "passive"))
    )
    (net (code "33") (name "/EA1") (class "Default")
      (node (ref "C15") (pin "1") (pinfunction "1_1") (pintype "passive"))
      (node (ref "POTE") (pin "11") (pinfunction "A2_11") (pintype "passive"))
      (node (ref "POTE") (pin "8") (pinfunction "A1_8") (pintype "passive"))
    )
    (net (code "34") (name "/EW2") (class "Default")
      (node (ref "AMP1") (pin "10") (pinfunction "+C_10") (pintype "bidirectional"))
      (node (ref "C16") (pin "1") (pinfunction "1_1") (pintype "passive"))
      (node (ref "POTE") (pin "13") (pinfunction "W2_13") (pintype "passive"))
      (node (ref "POTE") (pin "17") (pinfunction "A3_17") (pintype "passive"))
    )
    (net (code "35") (name "/FA3") (class "Default")
      (node (ref "C19") (pin "1") (pinfunction "1_1") (pintype "passive"))
      (node (ref "POTF") (pin "17") (pinfunction "A3_17") (pintype "passive"))
      (node (ref "POTG") (pin "3") (pinfunction "A0_3") (pintype "passive"))
    )
    (net (code "36") (name "/FW1") (class "Default")
      (node (ref "AMP1") (pin "12") (pinfunction "+D_12") (pintype "bidirectional"))
      (node (ref "BPF6GS2TEST") (pin "1") (pinfunction "1_1") (pintype "passive"))
      (node (ref "C18") (pin "1") (pinfunction "1_1") (pintype "passive"))
      (node (ref "POTF") (pin "11") (pinfunction "A2_11") (pintype "passive"))
      (node (ref "POTF") (pin "6") (pinfunction "W1_6") (pintype "passive"))
    )
    (net (code "37") (name "/GW0") (class "Default")
      (node (ref "AMP2") (pin "3") (pinfunction "+A_3") (pintype "bidirectional"))
      (node (ref "BPF6GS3TEST") (pin "1") (pinfunction "1_1") (pintype "passive"))
      (node (ref "C20") (pin "1") (pinfunction "1_1") (pintype "passive"))
      (node (ref "POTG") (pin "1") (pinfunction "W0_1") (pintype "passive"))
      (node (ref "POTG") (pin "8") (pinfunction "A1_8") (pintype "passive"))
    )
    (net (code "38") (name "/HPF1IN") (class "Default")
      (node (ref "A3IDEMUX") (pin "15") (pinfunction "A2_15_15") (pintype "bidirectional"))
      (node (ref "AI1DEMUX") (pin "15") (pinfunction "A2_15_15") (pintype "bidirectional"))
      (node (ref "AI2DEMUX") (pin "15") (pinfunction "A2_15_15") (pintype "bidirectional"))
      (node (ref "C7") (pin "2") (pinfunction "2_2") (pintype "passive"))
      (node (ref "HPF1INTEST") (pin "1") (pinfunction "1_1") (pintype "passive"))
    )
    (net (code "39") (name "/HPF1OUT") (class "Default")
      (node (ref "AMP0") (pin "8") (pinfunction "C_8") (pintype "bidirectional"))
      (node (ref "AMP0") (pin "9") (pinfunction "-C_9") (pintype "bidirectional"))
      (node (ref "AO1MUX") (pin "15") (pinfunction "A2_15_15") (pintype "bidirectional"))
      (node (ref "AO2MUX") (pin "15") (pinfunction "A2_15_15") (pintype "bidirectional"))
      (node (ref "AO3MUX") (pin "15") (pinfunction "A2_15_15") (pintype "bidirectional"))
      (node (ref "HPF1OUTTEST") (pin "1") (pinfunction "1_1") (pintype "passive"))
      (node (ref "R3") (pin "2") (pinfunction "2_2") (pintype "passive"))
    )
    (net (code "40") (name "/HPF5IN") (class "Default")
      (node (ref "A3IDEMUX") (pin "12") (pinfunction "A3_12_12") (pintype "bidirectional"))
      (node (ref "AI1DEMUX") (pin "12") (pinfunction "A3_12_12") (pintype "bidirectional"))
      (node (ref "AI2DEMUX") (pin "12") (pinfunction "A3_12_12") (pintype "bidirectional"))
      (node (ref "C8") (pin "2") (pinfunction "2_2") (pintype "passive"))
      (node (ref "HPF5INTEST") (pin "1") (pinfunction "1_1") (pintype "passive"))
    )
    (net (code "41") (name "/HPF5OUT") (class "Default")
      (node (ref "AMP0") (pin "13") (pinfunction "-D_13") (pintype "bidirectional"))
      (node (ref "AMP0") (pin "14") (pinfunction "D_14") (pintype "bidirectional"))
      (node (ref "AO1MUX") (pin "12") (pinfunction "A3_12_12") (pintype "bidirectional"))
      (node (ref "AO2MUX") (pin "12") (pinfunction "A3_12_12") (pintype "bidirectional"))
      (node (ref "AO3MUX") (pin "12") (pinfunction "A3_12_12") (pintype "bidirectional"))
      (node (ref "HPF5OUTTEST") (pin "1") (pinfunction "1_1") (pintype "passive"))
      (node (ref "R4") (pin "1") (pinfunction "1_1") (pintype "passive"))
    )
    (net (code "42") (name "/I2C1SCL") (class "Default")
      (node (ref "R28") (pin "1") (pinfunction "1_1") (pintype "passive"))
      (node (ref "U$2") (pin "4") (pinfunction "4_4") (pintype "passive"))
      (node (ref "U$4") (pin "17") (pinfunction "PA6_17") (pintype "passive"))
    )
    (net (code "43") (name "/I2C1SDA") (class "Default")
      (node (ref "R29") (pin "1") (pinfunction "1_1") (pintype "passive"))
      (node (ref "U$2") (pin "1") (pinfunction "1_1") (pintype "passive"))
      (node (ref "U$4") (pin "19") (pinfunction "PA7_19") (pintype "passive"))
    )
    (net (code "44") (name "/I2C2SCL") (class "Default")
      (node (ref "R26") (pin "1") (pinfunction "1_1") (pintype "passive"))
      (node (ref "SCLMUX") (pin "3") (pinfunction "COMIN_3_3") (pintype "bidirectional"))
      (node (ref "U$4") (pin "9") (pinfunction "PE4_9") (pintype "passive"))
    )
    (net (code "45") (name "/I2C2SDA") (class "Default")
      (node (ref "POTA") (pin "9") (pinfunction "SDA_9") (pintype "passive"))
      (node (ref "POTB") (pin "9") (pinfunction "SDA_9") (pintype "passive"))
      (node (ref "POTC") (pin "9") (pinfunction "SDA_9") (pintype "passive"))
      (node (ref "POTD") (pin "9") (pinfunction "SDA_9") (pintype "passive"))
      (node (ref "POTE") (pin "9") (pinfunction "SDA_9") (pintype "passive"))
      (node (ref "POTF") (pin "9") (pinfunction "SDA_9") (pintype "passive"))
      (node (ref "POTG") (pin "9") (pinfunction "SDA_9") (pintype "passive"))
      (node (ref "R27") (pin "1") (pinfunction "1_1") (pintype "passive"))
      (node (ref "U$4") (pin "11") (pinfunction "PE5_11") (pintype "passive"))
    )
    (net (code "46") (name "/LPF1IN") (class "Default")
      (node (ref "A3IDEMUX") (pin "13") (pinfunction "A0_13_13") (pintype "bidirectional"))
      (node (ref "AI1DEMUX") (pin "13") (pinfunction "A0_13_13") (pintype "bidirectional"))
      (node (ref "AI2DEMUX") (pin "13") (pinfunction "A0_13_13") (pintype "bidirectional"))
      (node (ref "LPF1INTEST") (pin "1") (pinfunction "1_1") (pintype "passive"))
      (node (ref "POTA") (pin "3") (pinfunction "A0_3") (pintype "passive"))
    )
    (net (code "47") (name "/LPF1OUT") (class "Default")
      (node (ref "AMP0") (pin "1") (pinfunction "A_1") (pintype "bidirectional"))
      (node (ref "AMP0") (pin "2") (pinfunction "-A_2") (pintype "bidirectional"))
      (node (ref "AO1MUX") (pin "13") (pinfunction "A0_13_13") (pintype "bidirectional"))
      (node (ref "AO2MUX") (pin "13") (pinfunction "A0_13_13") (pintype "bidirectional"))
      (node (ref "AO3MUX") (pin "13") (pinfunction "A0_13_13") (pintype "bidirectional"))
      (node (ref "LPF1OUTTEST") (pin "1") (pinfunction "1_1") (pintype "passive"))
      (node (ref "R1") (pin "1") (pinfunction "1_1") (pintype "passive"))
    )
    (net (code "48") (name "/LPF5IN") (class "Default")
      (node (ref "A3IDEMUX") (pin "14") (pinfunction "A1_14_14") (pintype "bidirectional"))
      (node (ref "AI1DEMUX") (pin "14") (pinfunction "A1_14_14") (pintype "bidirectional"))
      (node (ref "AI2DEMUX") (pin "14") (pinfunction "A1_14_14") (pintype "bidirectional"))
      (node (ref "LPF5INTEST") (pin "1") (pinfunction "1_1") (pintype "passive"))
      (node (ref "POTA") (pin "8") (pinfunction "A1_8") (pintype "passive"))
    )
    (net (code "49") (name "/LPF5OUT") (class "Default")
      (node (ref "AMP0") (pin "6") (pinfunction "-B_6") (pintype "bidirectional"))
      (node (ref "AMP0") (pin "7") (pinfunction "B_7") (pintype "bidirectional"))
      (node (ref "AO1MUX") (pin "14") (pinfunction "A1_14_14") (pintype "bidirectional"))
      (node (ref "AO2MUX") (pin "14") (pinfunction "A1_14_14") (pintype "bidirectional"))
      (node (ref "AO3MUX") (pin "14") (pinfunction "A1_14_14") (pintype "bidirectional"))
      (node (ref "LPF5OUTTEST") (pin "1") (pinfunction "1_1") (pintype "passive"))
      (node (ref "R2") (pin "1") (pinfunction "1_1") (pintype "passive"))
    )
    (net (code "50") (name "/N$136") (class "Default")
      (node (ref "AMP1") (pin "9") (pinfunction "-C_9") (pintype "bidirectional"))
      (node (ref "BPF6GS1TEST") (pin "1") (pinfunction "1_1") (pintype "passive"))
      (node (ref "R10") (pin "1") (pinfunction "1_1") (pintype "passive"))
      (node (ref "R8") (pin "2") (pinfunction "2_2") (pintype "passive"))
    )
    (net (code "51") (name "/N$140") (class "Default")
      (node (ref "AMP1") (pin "13") (pinfunction "-D_13") (pintype "bidirectional"))
      (node (ref "R11") (pin "1") (pinfunction "1_1") (pintype "passive"))
      (node (ref "R9") (pin "1") (pinfunction "1_1") (pintype "passive"))
    )
    (net (code "52") (name "/NCPOT") (class "Default")
      (node (ref "R15") (pin "2") (pinfunction "2_2") (pintype "passive"))
      (node (ref "SCLMUX") (pin "4") (pinfunction "A7_4_4") (pintype "bidirectional"))
    )
    (net (code "53") (name "/NODEA") (class "Default")
      (node (ref "AMP0") (pin "10") (pinfunction "+C_10") (pintype "bidirectional"))
      (node (ref "C7") (pin "1") (pinfunction "1_1") (pintype "passive"))
      (node (ref "HPF1PREAMPTEST") (pin "1") (pinfunction "1_1") (pintype "passive"))
      (node (ref "POTB") (pin "11") (pinfunction "A2_11") (pintype "passive"))
      (node (ref "POTB") (pin "17") (pinfunction "A3_17") (pintype "passive"))
    )
    (net (code "54") (name "/NODEB") (class "Default")
      (node (ref "AMP0") (pin "12") (pinfunction "+D_12") (pintype "bidirectional"))
      (node (ref "C12") (pin "1") (pinfunction "1_1") (pintype "passive"))
      (node (ref "HPF5PREAMPTEST") (pin "1") (pinfunction "1_1") (pintype "passive"))
      (node (ref "POTD") (pin "3") (pinfunction "A0_3") (pintype "passive"))
      (node (ref "POTD") (pin "8") (pinfunction "A1_8") (pintype "passive"))
    )
    (net (code "55") (name "/NODEC") (class "Default")
      (node (ref "C13") (pin "1") (pinfunction "1_1") (pintype "passive"))
      (node (ref "POTD") (pin "11") (pinfunction "A2_11") (pintype "passive"))
      (node (ref "POTD") (pin "17") (pinfunction "A3_17") (pintype "passive"))
    )
    (net (code "56") (name "/NODED") (class "Default")
      (node (ref "C17") (pin "1") (pinfunction "1_1") (pintype "passive"))
      (node (ref "POTF") (pin "3") (pinfunction "A0_3") (pintype "passive"))
      (node (ref "POTF") (pin "8") (pinfunction "A1_8") (pintype "passive"))
    )
    (net (code "57") (name "/NODEE") (class "Default")
      (node (ref "60HZPREAMPTEST") (pin "1") (pinfunction "1_1") (pintype "passive"))
      (node (ref "AMP2") (pin "10") (pinfunction "+C_10") (pintype "bidirectional"))
      (node (ref "C22") (pin "1") (pinfunction "1_1") (pintype "passive"))
      (node (ref "R24") (pin "2") (pinfunction "2_2") (pintype "passive"))
    )
    (net (code "58") (name "/NODEF") (class "Default")
      (node (ref "C23") (pin "1") (pinfunction "1_1") (pintype "passive"))
      (node (ref "R23") (pin "2") (pinfunction "2_2") (pintype "passive"))
      (node (ref "R24") (pin "1") (pinfunction "1_1") (pintype "passive"))
    )
    (net (code "59") (name "/NODEG") (class "Default")
      (node (ref "C21") (pin "1") (pinfunction "1_1") (pintype "passive"))
      (node (ref "C22") (pin "2") (pinfunction "2_2") (pintype "passive"))
      (node (ref "R25") (pin "1") (pinfunction "1_1") (pintype "passive"))
    )
    (net (code "60") (name "/PASSTHRUIN") (class "Default")
      (node (ref "A3IDEMUX") (pin "4") (pinfunction "A7_4_4") (pintype "bidirectional"))
      (node (ref "AI1DEMUX") (pin "4") (pinfunction "A7_4_4") (pintype "bidirectional"))
      (node (ref "AI2DEMUX") (pin "4") (pinfunction "A7_4_4") (pintype "bidirectional"))
      (node (ref "AMP2") (pin "12") (pinfunction "+D_12") (pintype "bidirectional"))
      (node (ref "PASSTHRUTEST") (pin "1") (pinfunction "1_1") (pintype "passive"))
    )
    (net (code "61") (name "/PASSTHRUOUT") (class "Default")
      (node (ref "AMP2") (pin "13") (pinfunction "-D_13") (pintype "bidirectional"))
      (node (ref "AMP2") (pin "14") (pinfunction "D_14") (pintype "bidirectional"))
      (node (ref "AO1MUX") (pin "4") (pinfunction "A7_4_4") (pintype "bidirectional"))
      (node (ref "AO2MUX") (pin "4") (pinfunction "A7_4_4") (pintype "bidirectional"))
      (node (ref "AO3MUX") (pin "4") (pinfunction "A7_4_4") (pintype "bidirectional"))
    )
    (net (code "62") (name "/S1INPUT") (class "Default")
      (node (ref "AI1DEMUX") (pin "3") (pinfunction "COMIN_3_3") (pintype "bidirectional"))
      (node (ref "S1INPUT") (pin "3") (pinfunction "3_3") (pintype "passive"))
      (node (ref "SENSOR1INPUT") (pin "1") (pinfunction "1_1") (pintype "passive"))
    )
    (net (code "63") (name "/S2INPUT") (class "Default")
      (node (ref "AI2DEMUX") (pin "3") (pinfunction "COMIN_3_3") (pintype "bidirectional"))
      (node (ref "S2INPUT") (pin "3") (pinfunction "3_3") (pintype "passive"))
      (node (ref "SENSOR2INPUT") (pin "1") (pinfunction "1_1") (pintype "passive"))
    )
    (net (code "64") (name "/S3INPUT") (class "Default")
      (node (ref "A3IDEMUX") (pin "3") (pinfunction "COMIN_3_3") (pintype "bidirectional"))
      (node (ref "S3INPUT") (pin "3") (pinfunction "3_3") (pintype "passive"))
      (node (ref "SENSOR3INPUT") (pin "1") (pinfunction "1_1") (pintype "passive"))
    )
    (net (code "65") (name "/SCLA") (class "Default")
      (node (ref "POTA") (pin "14") (pinfunction "SCL_14") (pintype "passive"))
      (node (ref "R22") (pin "2") (pinfunction "2_2") (pintype "passive"))
      (node (ref "SCLMUX") (pin "13") (pinfunction "A0_13_13") (pintype "bidirectional"))
    )
    (net (code "66") (name "/SCLB") (class "Default")
      (node (ref "POTB") (pin "14") (pinfunction "SCL_14") (pintype "passive"))
      (node (ref "R21") (pin "2") (pinfunction "2_2") (pintype "passive"))
      (node (ref "SCLMUX") (pin "14") (pinfunction "A1_14_14") (pintype "bidirectional"))
    )
    (net (code "67") (name "/SCLC") (class "Default")
      (node (ref "POTC") (pin "14") (pinfunction "SCL_14") (pintype "passive"))
      (node (ref "R20") (pin "2") (pinfunction "2_2") (pintype "passive"))
      (node (ref "SCLMUX") (pin "15") (pinfunction "A2_15_15") (pintype "bidirectional"))
    )
    (net (code "68") (name "/SCLD") (class "Default")
      (node (ref "POTD") (pin "14") (pinfunction "SCL_14") (pintype "passive"))
      (node (ref "R19") (pin "2") (pinfunction "2_2") (pintype "passive"))
      (node (ref "SCLMUX") (pin "12") (pinfunction "A3_12_12") (pintype "bidirectional"))
    )
    (net (code "69") (name "/SCLE") (class "Default")
      (node (ref "POTE") (pin "14") (pinfunction "SCL_14") (pintype "passive"))
      (node (ref "R18") (pin "2") (pinfunction "2_2") (pintype "passive"))
      (node (ref "SCLMUX") (pin "1") (pinfunction "A4_1_1") (pintype "bidirectional"))
    )
    (net (code "70") (name "/SCLF") (class "Default")
      (node (ref "POTF") (pin "14") (pinfunction "SCL_14") (pintype "passive"))
      (node (ref "R17") (pin "2") (pinfunction "2_2") (pintype "passive"))
      (node (ref "SCLMUX") (pin "5") (pinfunction "A5_5_5") (pintype "bidirectional"))
    )
    (net (code "71") (name "/SCLG") (class "Default")
      (node (ref "POTG") (pin "14") (pinfunction "SCL_14") (pintype "passive"))
      (node (ref "R16") (pin "2") (pinfunction "2_2") (pintype "passive"))
      (node (ref "SCLMUX") (pin "2") (pinfunction "A6_2_2") (pintype "bidirectional"))
    )
    (net (code "72") (name "/SCLS0") (class "Default")
      (node (ref "SCLMUX") (pin "11") (pinfunction "S0_11_11") (pintype "bidirectional"))
      (node (ref "U$4") (pin "27") (pinfunction "PC4_27") (pintype "passive"))
    )
    (net (code "73") (name "/SCLS1") (class "Default")
      (node (ref "SCLMUX") (pin "10") (pinfunction "S1_10_10") (pintype "bidirectional"))
      (node (ref "U$4") (pin "29") (pinfunction "PC5_29") (pintype "passive"))
    )
    (net (code "74") (name "/SCLS2") (class "Default")
      (node (ref "SCLMUX") (pin "9") (pinfunction "S2_9_9") (pintype "bidirectional"))
      (node (ref "U$4") (pin "31") (pinfunction "PC6_31") (pintype "passive"))
    )
    (net (code "75") (name "/SSIOCLK") (class "Default")
      (node (ref "U$1") (pin "1") (pinfunction "1_1") (pintype "passive"))
      (node (ref "U$4") (pin "40") (pinfunction "PA2_40") (pintype "passive"))
    )
    (net (code "76") (name "/SSIOFSS") (class "Default")
      (node (ref "U$1") (pin "5") (pinfunction "5_5") (pintype "passive"))
      (node (ref "U$4") (pin "38") (pinfunction "PA3_38") (pintype "passive"))
    )
    (net (code "77") (name "/SSIORX") (class "Default")
      (node (ref "U$1") (pin "3") (pinfunction "3_3") (pintype "passive"))
      (node (ref "U$4") (pin "36") (pinfunction "PA4_36") (pintype "passive"))
    )
    (net (code "78") (name "/SSIOTX") (class "Default")
      (node (ref "U$1") (pin "2") (pinfunction "2_2") (pintype "passive"))
      (node (ref "U$4") (pin "15") (pinfunction "PA5_15") (pintype "passive"))
    )
    (net (code "79") (name "/STAGE1OUT") (class "Default")
      (node (ref "AMP1") (pin "8") (pinfunction "C_8") (pintype "bidirectional"))
      (node (ref "C17") (pin "2") (pinfunction "2_2") (pintype "passive"))
      (node (ref "R8") (pin "1") (pinfunction "1_1") (pintype "passive"))
    )
    (net (code "80") (name "/STAGE2OUT") (class "Default")
      (node (ref "AMP1") (pin "14") (pinfunction "D_14") (pintype "bidirectional"))
      (node (ref "C19") (pin "2") (pinfunction "2_2") (pintype "passive"))
      (node (ref "R9") (pin "2") (pinfunction "2_2") (pintype "passive"))
    )
    (net (code "81") (name "GND") (class "Default")
      (node (ref "A3IDEMUX") (pin "6") (pinfunction "E_6_6") (pintype "bidirectional"))
      (node (ref "A3IDEMUX") (pin "7") (pinfunction "VEE_7_7") (pintype "bidirectional"))
      (node (ref "A3IDEMUX") (pin "8") (pinfunction "GND_8_8") (pintype "bidirectional"))
      (node (ref "AI1DEMUX") (pin "6") (pinfunction "E_6_6") (pintype "bidirectional"))
      (node (ref "AI1DEMUX") (pin "7") (pinfunction "VEE_7_7") (pintype "bidirectional"))
      (node (ref "AI1DEMUX") (pin "8") (pinfunction "GND_8_8") (pintype "bidirectional"))
      (node (ref "AI2DEMUX") (pin "6") (pinfunction "E_6_6") (pintype "bidirectional"))
      (node (ref "AI2DEMUX") (pin "7") (pinfunction "VEE_7_7") (pintype "bidirectional"))
      (node (ref "AI2DEMUX") (pin "8") (pinfunction "GND_8_8") (pintype "bidirectional"))
      (node (ref "AMP0") (pin "11") (pinfunction "-V_11") (pintype "bidirectional"))
      (node (ref "AMP1") (pin "11") (pinfunction "-V_11") (pintype "bidirectional"))
      (node (ref "AMP2") (pin "11") (pinfunction "-V_11") (pintype "bidirectional"))
      (node (ref "AO1MUX") (pin "6") (pinfunction "E_6_6") (pintype "bidirectional"))
      (node (ref "AO1MUX") (pin "7") (pinfunction "VEE_7_7") (pintype "bidirectional"))
      (node (ref "AO1MUX") (pin "8") (pinfunction "GND_8_8") (pintype "bidirectional"))
      (node (ref "AO2MUX") (pin "6") (pinfunction "E_6_6") (pintype "bidirectional"))
      (node (ref "AO2MUX") (pin "7") (pinfunction "VEE_7_7") (pintype "bidirectional"))
      (node (ref "AO2MUX") (pin "8") (pinfunction "GND_8_8") (pintype "bidirectional"))
      (node (ref "AO3MUX") (pin "6") (pinfunction "E_6_6") (pintype "bidirectional"))
      (node (ref "AO3MUX") (pin "7") (pinfunction "VEE_7_7") (pintype "bidirectional"))
      (node (ref "AO3MUX") (pin "8") (pinfunction "GND_8_8") (pintype "bidirectional"))
      (node (ref "C1") (pin "2") (pinfunction "2_2") (pintype "passive"))
      (node (ref "C14") (pin "2") (pinfunction "2_2") (pintype "passive"))
      (node (ref "C16") (pin "2") (pinfunction "2_2") (pintype "passive"))
      (node (ref "C18") (pin "2") (pinfunction "2_2") (pintype "passive"))
      (node (ref "C2") (pin "2") (pinfunction "2_2") (pintype "passive"))
      (node (ref "C20") (pin "2") (pinfunction "2_2") (pintype "passive"))
      (node (ref "C23") (pin "2") (pinfunction "2_2") (pintype "passive"))
      (node (ref "C3") (pin "2") (pinfunction "2_2") (pintype "passive"))
      (node (ref "C4") (pin "2") (pinfunction "2_2") (pintype "passive"))
      (node (ref "C5") (pin "2") (pinfunction "2_2") (pintype "passive"))
      (node (ref "C6") (pin "2") (pinfunction "2_2") (pintype "passive"))
      (node (ref "D1") (pin "C") (pinfunction "C_C") (pintype "passive"))
      (node (ref "POTA") (pin "10") (pinfunction "VSS_10") (pintype "power_in"))
      (node (ref "POTA") (pin "15") (pinfunction "DGND_15") (pintype "passive"))
      (node (ref "POTA") (pin "16") (pinfunction "AD1_16") (pintype "passive"))
      (node (ref "POTA") (pin "4") (pinfunction "AD0_4") (pintype "passive"))
      (node (ref "POTB") (pin "10") (pinfunction "VSS_10") (pintype "power_in"))
      (node (ref "POTB") (pin "15") (pinfunction "DGND_15") (pintype "passive"))
      (node (ref "POTB") (pin "16") (pinfunction "AD1_16") (pintype "passive"))
      (node (ref "POTB") (pin "19") (pinfunction "W3_19") (pintype "passive"))
      (node (ref "POTB") (pin "4") (pinfunction "AD0_4") (pintype "passive"))
      (node (ref "POTC") (pin "1") (pinfunction "W0_1") (pintype "passive"))
      (node (ref "POTC") (pin "10") (pinfunction "VSS_10") (pintype "power_in"))
      (node (ref "POTC") (pin "13") (pinfunction "W2_13") (pintype "passive"))
      (node (ref "POTC") (pin "15") (pinfunction "DGND_15") (pintype "passive"))
      (node (ref "POTC") (pin "16") (pinfunction "AD1_16") (pintype "passive"))
      (node (ref "POTC") (pin "19") (pinfunction "W3_19") (pintype "passive"))
      (node (ref "POTC") (pin "4") (pinfunction "AD0_4") (pintype "passive"))
      (node (ref "POTC") (pin "6") (pinfunction "W1_6") (pintype "passive"))
      (node (ref "POTD") (pin "10") (pinfunction "VSS_10") (pintype "power_in"))
      (node (ref "POTD") (pin "15") (pinfunction "DGND_15") (pintype "passive"))
      (node (ref "POTD") (pin "16") (pinfunction "AD1_16") (pintype "passive"))
      (node (ref "POTD") (pin "19") (pinfunction "W3_19") (pintype "passive"))
      (node (ref "POTD") (pin "4") (pinfunction "AD0_4") (pintype "passive"))
      (node (ref "POTD") (pin "6") (pinfunction "W1_6") (pintype "passive"))
      (node (ref "POTE") (pin "10") (pinfunction "VSS_10") (pintype "power_in"))
      (node (ref "POTE") (pin "15") (pinfunction "DGND_15") (pintype "passive"))
      (node (ref "POTE") (pin "16") (pinfunction "AD1_16") (pintype "passive"))
      (node (ref "POTE") (pin "4") (pinfunction "AD0_4") (pintype "passive"))
      (node (ref "POTE") (pin "6") (pinfunction "W1_6") (pintype "passive"))
      (node (ref "POTF") (pin "1") (pinfunction "W0_1") (pintype "passive"))
      (node (ref "POTF") (pin "10") (pinfunction "VSS_10") (pintype "power_in"))
      (node (ref "POTF") (pin "15") (pinfunction "DGND_15") (pintype "passive"))
      (node (ref "POTF") (pin "16") (pinfunction "AD1_16") (pintype "passive"))
      (node (ref "POTF") (pin "19") (pinfunction "W3_19") (pintype "passive"))
      (node (ref "POTF") (pin "4") (pinfunction "AD0_4") (pintype "passive"))
      (node (ref "POTG") (pin "10") (pinfunction "VSS_10") (pintype "power_in"))
      (node (ref "POTG") (pin "15") (pinfunction "DGND_15") (pintype "passive"))
      (node (ref "POTG") (pin "16") (pinfunction "AD1_16") (pintype "passive"))
      (node (ref "POTG") (pin "4") (pinfunction "AD0_4") (pintype "passive"))
      (node (ref "R1") (pin "2") (pinfunction "2_2") (pintype "passive"))
      (node (ref "R10") (pin "2") (pinfunction "2_2") (pintype "passive"))
      (node (ref "R11") (pin "2") (pinfunction "2_2") (pintype "passive"))
      (node (ref "R13") (pin "2") (pinfunction "2_2") (pintype "passive"))
      (node (ref "R14") (pin "2") (pinfunction "2_2") (pintype "passive"))
      (node (ref "R2") (pin "2") (pinfunction "2_2") (pintype "passive"))
      (node (ref "R25") (pin "2") (pinfunction "2_2") (pintype "passive"))
      (node (ref "R3") (pin "1") (pinfunction "1_1") (pintype "passive"))
      (node (ref "R30") (pin "1") (pinfunction "1_1") (pintype "passive"))
      (node (ref "R4") (pin "2") (pinfunction "2_2") (pintype "passive"))
      (node (ref "R5") (pin "1") (pinfunction "1_1") (pintype "passive"))
      (node (ref "R7") (pin "1") (pinfunction "1_1") (pintype "passive"))
      (node (ref "S1INPUT") (pin "2") (pinfunction "2_2") (pintype "passive"))
      (node (ref "S2INPUT") (pin "2") (pinfunction "2_2") (pintype "passive"))
      (node (ref "S3INPUT") (pin "2") (pinfunction "2_2") (pintype "passive"))
      (node (ref "SCLMUX") (pin "6") (pinfunction "E_6_6") (pintype "bidirectional"))
      (node (ref "SCLMUX") (pin "7") (pinfunction "VEE_7_7") (pintype "bidirectional"))
      (node (ref "SCLMUX") (pin "8") (pinfunction "GND_8_8") (pintype "bidirectional"))
      (node (ref "U$1") (pin "6") (pinfunction "6_6") (pintype "passive"))
      (node (ref "U$2") (pin "3") (pinfunction "3_3") (pintype "passive"))
      (node (ref "U$4") (pin "22") (pinfunction "GND1_22") (pintype "passive"))
      (node (ref "U$4") (pin "4") (pinfunction "GND_4") (pintype "passive"))
    )
    (net (code "82") (name "Net-(AMP2-+B)") (class "Default")
      (node (ref "AMP2") (pin "1") (pinfunction "A_1") (pintype "bidirectional"))
      (node (ref "AMP2") (pin "5") (pinfunction "+B_5") (pintype "bidirectional"))
      (node (ref "R12") (pin "1") (pinfunction "1_1") (pintype "passive"))
    )
    (net (code "83") (name "Net-(AMP2--A)") (class "Default")
      (node (ref "AMP2") (pin "2") (pinfunction "-A_2") (pintype "bidirectional"))
      (node (ref "R12") (pin "2") (pinfunction "2_2") (pintype "passive"))
      (node (ref "R30") (pin "2") (pinfunction "2_2") (pintype "passive"))
    )
    (net (code "84") (name "Net-(CL_RES-Pad1)") (class "Default")
      (node (ref "CL_RES") (pin "1") (pinfunction "1_1") (pintype "passive"))
      (node (ref "D1") (pin "A") (pinfunction "A_A") (pintype "passive"))
    )
    (net (code "85") (name "unconnected-(POTA-B0-Pad2)") (class "Default")
      (node (ref "POTA") (pin "2") (pinfunction "B0_2") (pintype "passive"))
    )
    (net (code "86") (name "unconnected-(POTA-B1-Pad7)") (class "Default")
      (node (ref "POTA") (pin "7") (pinfunction "B1_7") (pintype "passive"))
    )
    (net (code "87") (name "unconnected-(POTA-B2-Pad12)") (class "Default")
      (node (ref "POTA") (pin "12") (pinfunction "B2_12") (pintype "passive"))
    )
    (net (code "88") (name "unconnected-(POTA-B3-Pad18)") (class "Default")
      (node (ref "POTA") (pin "18") (pinfunction "B3_18") (pintype "passive"))
    )
    (net (code "89") (name "unconnected-(POTB-B0-Pad2)") (class "Default")
      (node (ref "POTB") (pin "2") (pinfunction "B0_2") (pintype "passive"))
    )
    (net (code "90") (name "unconnected-(POTB-B1-Pad7)") (class "Default")
      (node (ref "POTB") (pin "7") (pinfunction "B1_7") (pintype "passive"))
    )
    (net (code "91") (name "unconnected-(POTB-B2-Pad12)") (class "Default")
      (node (ref "POTB") (pin "12") (pinfunction "B2_12") (pintype "passive"))
    )
    (net (code "92") (name "unconnected-(POTB-B3-Pad18)") (class "Default")
      (node (ref "POTB") (pin "18") (pinfunction "B3_18") (pintype "passive"))
    )
    (net (code "93") (name "unconnected-(POTC-B0-Pad2)") (class "Default")
      (node (ref "POTC") (pin "2") (pinfunction "B0_2") (pintype "passive"))
    )
    (net (code "94") (name "unconnected-(POTC-B1-Pad7)") (class "Default")
      (node (ref "POTC") (pin "7") (pinfunction "B1_7") (pintype "passive"))
    )
    (net (code "95") (name "unconnected-(POTC-B2-Pad12)") (class "Default")
      (node (ref "POTC") (pin "12") (pinfunction "B2_12") (pintype "passive"))
    )
    (net (code "96") (name "unconnected-(POTC-B3-Pad18)") (class "Default")
      (node (ref "POTC") (pin "18") (pinfunction "B3_18") (pintype "passive"))
    )
    (net (code "97") (name "unconnected-(POTD-B0-Pad2)") (class "Default")
      (node (ref "POTD") (pin "2") (pinfunction "B0_2") (pintype "passive"))
    )
    (net (code "98") (name "unconnected-(POTD-B1-Pad7)") (class "Default")
      (node (ref "POTD") (pin "7") (pinfunction "B1_7") (pintype "passive"))
    )
    (net (code "99") (name "unconnected-(POTD-B2-Pad12)") (class "Default")
      (node (ref "POTD") (pin "12") (pinfunction "B2_12") (pintype "passive"))
    )
    (net (code "100") (name "unconnected-(POTD-B3-Pad18)") (class "Default")
      (node (ref "POTD") (pin "18") (pinfunction "B3_18") (pintype "passive"))
    )
    (net (code "101") (name "unconnected-(POTE-B0-Pad2)") (class "Default")
      (node (ref "POTE") (pin "2") (pinfunction "B0_2") (pintype "passive"))
    )
    (net (code "102") (name "unconnected-(POTE-B1-Pad7)") (class "Default")
      (node (ref "POTE") (pin "7") (pinfunction "B1_7") (pintype "passive"))
    )
    (net (code "103") (name "unconnected-(POTE-B2-Pad12)") (class "Default")
      (node (ref "POTE") (pin "12") (pinfunction "B2_12") (pintype "passive"))
    )
    (net (code "104") (name "unconnected-(POTE-B3-Pad18)") (class "Default")
      (node (ref "POTE") (pin "18") (pinfunction "B3_18") (pintype "passive"))
    )
    (net (code "105") (name "unconnected-(POTF-B0-Pad2)") (class "Default")
      (node (ref "POTF") (pin "2") (pinfunction "B0_2") (pintype "passive"))
    )
    (net (code "106") (name "unconnected-(POTF-B1-Pad7)") (class "Default")
      (node (ref "POTF") (pin "7") (pinfunction "B1_7") (pintype "passive"))
    )
    (net (code "107") (name "unconnected-(POTF-B2-Pad12)") (class "Default")
      (node (ref "POTF") (pin "12") (pinfunction "B2_12") (pintype "passive"))
    )
    (net (code "108") (name "unconnected-(POTF-B3-Pad18)") (class "Default")
      (node (ref "POTF") (pin "18") (pinfunction "B3_18") (pintype "passive"))
    )
    (net (code "109") (name "unconnected-(POTG-A2-Pad11)") (class "Default")
      (node (ref "POTG") (pin "11") (pinfunction "A2_11") (pintype "passive"))
    )
    (net (code "110") (name "unconnected-(POTG-A3-Pad17)") (class "Default")
      (node (ref "POTG") (pin "17") (pinfunction "A3_17") (pintype "passive"))
    )
    (net (code "111") (name "unconnected-(POTG-B0-Pad2)") (class "Default")
      (node (ref "POTG") (pin "2") (pinfunction "B0_2") (pintype "passive"))
    )
    (net (code "112") (name "unconnected-(POTG-B1-Pad7)") (class "Default")
      (node (ref "POTG") (pin "7") (pinfunction "B1_7") (pintype "passive"))
    )
    (net (code "113") (name "unconnected-(POTG-B2-Pad12)") (class "Default")
      (node (ref "POTG") (pin "12") (pinfunction "B2_12") (pintype "passive"))
    )
    (net (code "114") (name "unconnected-(POTG-B3-Pad18)") (class "Default")
      (node (ref "POTG") (pin "18") (pinfunction "B3_18") (pintype "passive"))
    )
    (net (code "115") (name "unconnected-(POTG-W2-Pad13)") (class "Default")
      (node (ref "POTG") (pin "13") (pinfunction "W2_13") (pintype "passive"))
    )
    (net (code "116") (name "unconnected-(POTG-W3-Pad19)") (class "Default")
      (node (ref "POTG") (pin "19") (pinfunction "W3_19") (pintype "passive"))
    )
    (net (code "117") (name "unconnected-(U$4-PC7-Pad33)") (class "Default")
      (node (ref "U$4") (pin "33") (pinfunction "PC7_33") (pintype "passive"))
    )
    (net (code "118") (name "unconnected-(U$4-PD0-Pad6)") (class "Default")
      (node (ref "U$4") (pin "6") (pinfunction "PD0_6") (pintype "passive"))
    )
    (net (code "119") (name "unconnected-(U$4-PD1-Pad8)") (class "Default")
      (node (ref "U$4") (pin "8") (pinfunction "PD1_8") (pintype "passive"))
    )
    (net (code "120") (name "unconnected-(U$4-PD2-Pad10)") (class "Default")
      (node (ref "U$4") (pin "10") (pinfunction "PD2_10") (pintype "passive"))
    )
    (net (code "121") (name "unconnected-(U$4-PD3-Pad12)") (class "Default")
      (node (ref "U$4") (pin "12") (pinfunction "PD3_12") (pintype "passive"))
    )
    (net (code "122") (name "unconnected-(U$4-PD6-Pad35)") (class "Default")
      (node (ref "U$4") (pin "35") (pinfunction "PD6_35") (pintype "passive"))
    )
    (net (code "123") (name "unconnected-(U$4-PD7-Pad37)") (class "Default")
      (node (ref "U$4") (pin "37") (pinfunction "PD7_37") (pintype "passive"))
    )
    (net (code "124") (name "unconnected-(U$4-PE0-Pad26)") (class "Default")
      (node (ref "U$4") (pin "26") (pinfunction "PE0_26") (pintype "passive"))
    )
    (net (code "125") (name "unconnected-(U$4-PF1-Pad20)") (class "Default")
      (node (ref "U$4") (pin "20") (pinfunction "PF1_20") (pintype "passive"))
    )
    (net (code "126") (name "unconnected-(U$4-PF2-Pad21)") (class "Default")
      (node (ref "U$4") (pin "21") (pinfunction "PF2_21") (pintype "passive"))
    )
    (net (code "127") (name "unconnected-(U$4-PF3-Pad23)") (class "Default")
      (node (ref "U$4") (pin "23") (pinfunction "PF3_23") (pintype "passive"))
    )
    (net (code "128") (name "unconnected-(U$4-PF4-Pad39)") (class "Default")
      (node (ref "U$4") (pin "39") (pinfunction "PF4_39") (pintype "passive"))
    )
    (net (code "129") (name "unconnected-(U$4-RESET-Pad30)") (class "Default")
      (node (ref "U$4") (pin "30") (pinfunction "RESET_30") (pintype "passive"))
    )
    (net (code "130") (name "unconnected-(U$4-VBUS-Pad2)") (class "Default")
      (node (ref "U$4") (pin "2") (pinfunction "VBUS_2") (pintype "passive"))
    )
  )
)
